# ROM-el_Adapter.net
KiCad netlist of a schematic drawn in EAGLE
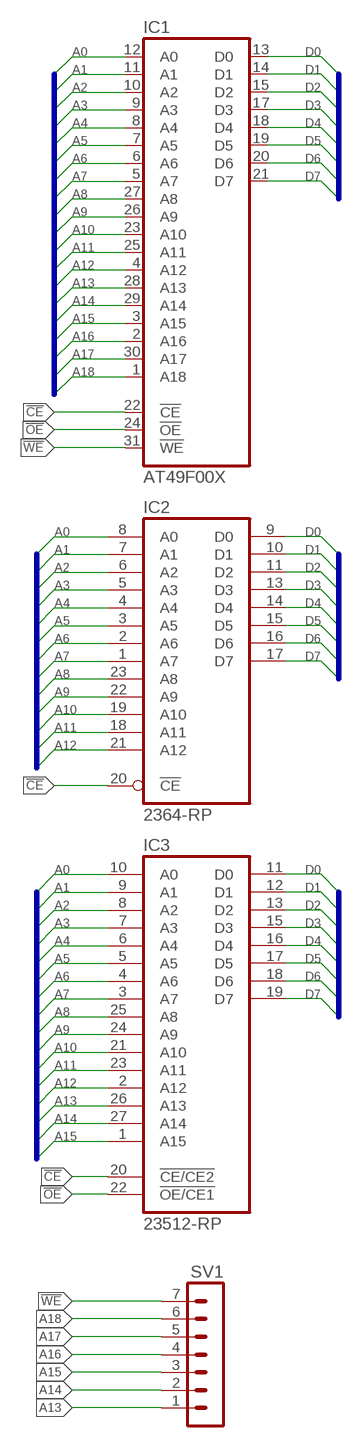
[diagram p0: schematic, sheet 1]

(export (version "E")
  (design (tool "Eeschema 10.0.6"))
  (components
    (comp (ref "IC1")
      (value "AT49F00X")
      (footprint "eagle-import:DIL32-RP")
      (libsource (lib "eagle-import") (part "SST39SF040APHR"))
    )
    (comp (ref "IC2")
      (value "2364-RP")
      (footprint "eagle-import:DIL24-ROUNDPAD")
      (libsource (lib "eagle-import") (part "2364-RP"))
    )
    (comp (ref "IC3")
      (value "23512-RP")
      (footprint "eagle-import:DIL28-ROUNDPAD")
      (libsource (lib "eagle-import") (part "23512-RP"))
    )
    (comp (ref "SV1")
      (value "MA07-1")
      (footprint "eagle-import:MA07-1")
      (libsource (lib "eagle-import") (part "MA07-1"))
    )
  )
  (nets
    (net (code "1") (name "/A0") (class "Default")
      (node (ref "IC1") (pin "12") (pinfunction "A0_12") (pintype "input"))
      (node (ref "IC2") (pin "8") (pinfunction "A0_8") (pintype "bidirectional"))
      (node (ref "IC3") (pin "10") (pinfunction "A0_10") (pintype "input"))
    )
    (net (code "2") (name "/A1") (class "Default")
      (node (ref "IC1") (pin "11") (pinfunction "A1_11") (pintype "input"))
      (node (ref "IC2") (pin "7") (pinfunction "A1_7") (pintype "bidirectional"))
      (node (ref "IC3") (pin "9") (pinfunction "A1_9") (pintype "input"))
    )
    (net (code "3") (name "/A2") (class "Default")
      (node (ref "IC1") (pin "10") (pinfunction "A2_10") (pintype "input"))
      (node (ref "IC2") (pin "6") (pinfunction "A2_6") (pintype "bidirectional"))
      (node (ref "IC3") (pin "8") (pinfunction "A2_8") (pintype "input"))
    )
    (net (code "4") (name "/A3") (class "Default")
      (node (ref "IC1") (pin "9") (pinfunction "A3_9") (pintype "input"))
      (node (ref "IC2") (pin "5") (pinfunction "A3_5") (pintype "bidirectional"))
      (node (ref "IC3") (pin "7") (pinfunction "A3_7") (pintype "input"))
    )
    (net (code "5") (name "/A4") (class "Default")
      (node (ref "IC1") (pin "8") (pinfunction "A4_8") (pintype "input"))
      (node (ref "IC2") (pin "4") (pinfunction "A4_4") (pintype "bidirectional"))
      (node (ref "IC3") (pin "6") (pinfunction "A4_6") (pintype "input"))
    )
    (net (code "6") (name "/A5") (class "Default")
      (node (ref "IC1") (pin "7") (pinfunction "A5_7") (pintype "input"))
      (node (ref "IC2") (pin "3") (pinfunction "A5_3") (pintype "bidirectional"))
      (node (ref "IC3") (pin "5") (pinfunction "A5_5") (pintype "input"))
    )
    (net (code "7") (name "/A6") (class "Default")
      (node (ref "IC1") (pin "6") (pinfunction "A6_6") (pintype "input"))
      (node (ref "IC2") (pin "2") (pinfunction "A6_2") (pintype "bidirectional"))
      (node (ref "IC3") (pin "4") (pinfunction "A6_4") (pintype "input"))
    )
    (net (code "8") (name "/A7") (class "Default")
      (node (ref "IC1") (pin "5") (pinfunction "A7_5") (pintype "input"))
      (node (ref "IC2") (pin "1") (pinfunction "A7_1") (pintype "bidirectional"))
      (node (ref "IC3") (pin "3") (pinfunction "A7_3") (pintype "input"))
    )
    (net (code "9") (name "/A8") (class "Default")
      (node (ref "IC1") (pin "27") (pinfunction "A8_27") (pintype "input"))
      (node (ref "IC2") (pin "23") (pinfunction "A8_23") (pintype "bidirectional"))
      (node (ref "IC3") (pin "25") (pinfunction "A8_25") (pintype "input"))
    )
    (net (code "10") (name "/A9") (class "Default")
      (node (ref "IC1") (pin "26") (pinfunction "A9_26") (pintype "input"))
      (node (ref "IC2") (pin "22") (pinfunction "A9_22") (pintype "bidirectional"))
      (node (ref "IC3") (pin "24") (pinfunction "A9_24") (pintype "input"))
    )
    (net (code "11") (name "/A10") (class "Default")
      (node (ref "IC1") (pin "23") (pinfunction "A10_23") (pintype "input"))
      (node (ref "IC2") (pin "19") (pinfunction "A10_19") (pintype "bidirectional"))
      (node (ref "IC3") (pin "21") (pinfunction "A10_21") (pintype "input"))
    )
    (net (code "12") (name "/A11") (class "Default")
      (node (ref "IC1") (pin "25") (pinfunction "A11_25") (pintype "input"))
      (node (ref "IC2") (pin "18") (pinfunction "A11_18") (pintype "bidirectional"))
      (node (ref "IC3") (pin "23") (pinfunction "A11_23") (pintype "input"))
    )
    (net (code "13") (name "/A12") (class "Default")
      (node (ref "IC1") (pin "4") (pinfunction "A12_4") (pintype "input"))
      (node (ref "IC2") (pin "21") (pinfunction "A12_21") (pintype "bidirectional"))
      (node (ref "IC3") (pin "2") (pinfunction "A12_2") (pintype "input"))
    )
    (net (code "14") (name "/D0") (class "Default")
      (node (ref "IC1") (pin "13") (pinfunction "D0_13") (pintype "bidirectional"))
      (node (ref "IC2") (pin "9") (pinfunction "D0_9") (pintype "tri_state"))
      (node (ref "IC3") (pin "11") (pinfunction "D0_11") (pintype "tri_state"))
    )
    (net (code "15") (name "/D1") (class "Default")
      (node (ref "IC1") (pin "14") (pinfunction "D1_14") (pintype "bidirectional"))
      (node (ref "IC2") (pin "10") (pinfunction "D1_10") (pintype "tri_state"))
      (node (ref "IC3") (pin "12") (pinfunction "D1_12") (pintype "tri_state"))
    )
    (net (code "16") (name "/D2") (class "Default")
      (node (ref "IC1") (pin "15") (pinfunction "D2_15") (pintype "bidirectional"))
      (node (ref "IC2") (pin "11") (pinfunction "D2_11") (pintype "tri_state"))
      (node (ref "IC3") (pin "13") (pinfunction "D2_13") (pintype "tri_state"))
    )
    (net (code "17") (name "/D3") (class "Default")
      (node (ref "IC1") (pin "17") (pinfunction "D3_17") (pintype "bidirectional"))
      (node (ref "IC2") (pin "13") (pinfunction "D3_13") (pintype "tri_state"))
      (node (ref "IC3") (pin "15") (pinfunction "D3_15") (pintype "tri_state"))
    )
    (net (code "18") (name "/D4") (class "Default")
      (node (ref "IC1") (pin "18") (pinfunction "D4_18") (pintype "bidirectional"))
      (node (ref "IC2") (pin "14") (pinfunction "D4_14") (pintype "tri_state"))
      (node (ref "IC3") (pin "16") (pinfunction "D4_16") (pintype "tri_state"))
    )
    (net (code "19") (name "/D5") (class "Default")
      (node (ref "IC1") (pin "19") (pinfunction "D5_19") (pintype "bidirectional"))
      (node (ref "IC2") (pin "15") (pinfunction "D5_15") (pintype "tri_state"))
      (node (ref "IC3") (pin "17") (pinfunction "D5_17") (pintype "tri_state"))
    )
    (net (code "20") (name "/D6") (class "Default")
      (node (ref "IC1") (pin "20") (pinfunction "D6_20") (pintype "bidirectional"))
      (node (ref "IC2") (pin "16") (pinfunction "D6_16") (pintype "tri_state"))
      (node (ref "IC3") (pin "18") (pinfunction "D6_18") (pintype "tri_state"))
    )
    (net (code "21") (name "/D7") (class "Default")
      (node (ref "IC1") (pin "21") (pinfunction "D7_21") (pintype "bidirectional"))
      (node (ref "IC2") (pin "17") (pinfunction "D7_17") (pintype "tri_state"))
      (node (ref "IC3") (pin "19") (pinfunction "D7_19") (pintype "tri_state"))
    )
    (net (code "22") (name "/~{CE}") (class "Default")
      (node (ref "IC1") (pin "22") (pinfunction "~{CE}_22") (pintype "input"))
      (node (ref "IC2") (pin "20") (pinfunction "~{CE}_20") (pintype "input"))
      (node (ref "IC3") (pin "20") (pinfunction "~{CE/CE2}_20") (pintype "input"))
    )
    (net (code "23") (name "/~{OE}") (class "Default")
      (node (ref "IC1") (pin "24") (pinfunction "~{OE}_24") (pintype "input"))
      (node (ref "IC3") (pin "22") (pinfunction "~{OE/CE1}_22") (pintype "input"))
    )
    (net (code "24") (name "/~{WE}") (class "Default")
      (node (ref "IC1") (pin "31") (pinfunction "~{WE}_31") (pintype "input"))
      (node (ref "SV1") (pin "7") (pinfunction "7_7") (pintype "passive"))
    )
    (net (code "25") (name "A13") (class "Default")
      (node (ref "IC1") (pin "28") (pinfunction "A13_28") (pintype "input"))
      (node (ref "IC3") (pin "26") (pinfunction "A13_26") (pintype "input"))
      (node (ref "SV1") (pin "1") (pinfunction "1_1") (pintype "passive"))
    )
    (net (code "26") (name "A14") (class "Default")
      (node (ref "IC1") (pin "29") (pinfunction "A14_29") (pintype "input"))
      (node (ref "IC3") (pin "27") (pinfunction "A14_27") (pintype "input"))
      (node (ref "SV1") (pin "2") (pinfunction "2_2") (pintype "passive"))
    )
    (net (code "27") (name "A15") (class "Default")
      (node (ref "IC1") (pin "3") (pinfunction "A15_3") (pintype "input"))
      (node (ref "IC3") (pin "1") (pinfunction "A15_1") (pintype "input"))
      (node (ref "SV1") (pin "3") (pinfunction "3_3") (pintype "passive"))
    )
    (net (code "28") (name "A16") (class "Default")
      (node (ref "IC1") (pin "2") (pinfunction "A16_2") (pintype "input"))
      (node (ref "SV1") (pin "4") (pinfunction "4_4") (pintype "passive"))
    )
    (net (code "29") (name "A17") (class "Default")
      (node (ref "IC1") (pin "30") (pinfunction "A17_30") (pintype "input"))
      (node (ref "SV1") (pin "5") (pinfunction "5_5") (pintype "passive"))
    )
    (net (code "30") (name "A18") (class "Default")
      (node (ref "IC1") (pin "1") (pinfunction "A18_1") (pintype "input"))
      (node (ref "SV1") (pin "6") (pinfunction "6_6") (pintype "passive"))
    )
  )
)
